# V1.net
KiCad netlist of a schematic drawn in EAGLE
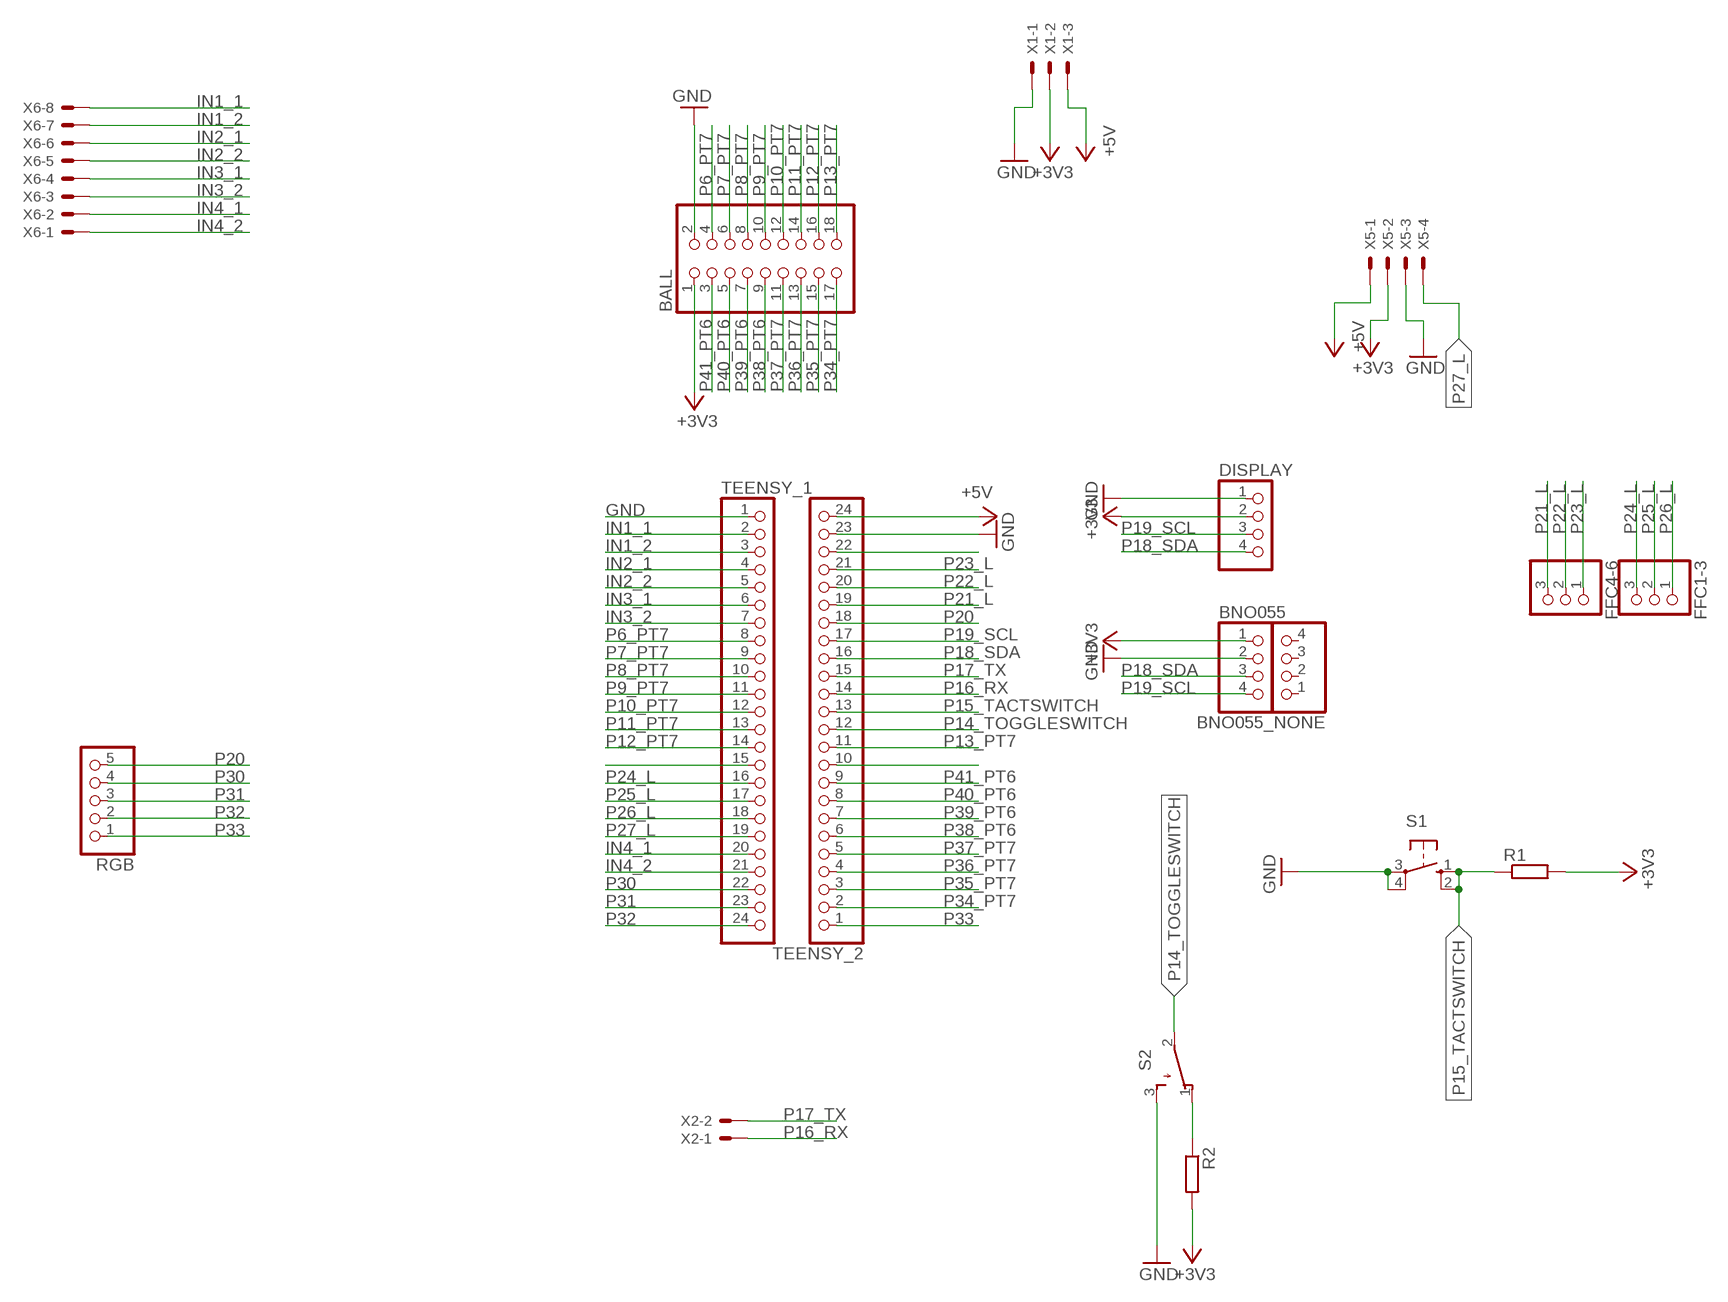
[diagram p0: schematic, sheet 1]

(export (version "E")
  (design (tool "Eeschema 10.0.6"))
  (components
    (comp (ref "BALL")
      (value "PINHD-2X9")
      (footprint "eagle-import:2X09")
      (libsource (lib "eagle-import") (part "PINHD-2X9"))
    )
    (comp (ref "BNO055")
      (value "PINHD-1X4")
      (footprint "eagle-import:1X04")
      (libsource (lib "eagle-import") (part "PINHD-1X4"))
    )
    (comp (ref "BNO055_NONE")
      (value "PINHD-1X4")
      (footprint "eagle-import:1X04")
      (libsource (lib "eagle-import") (part "PINHD-1X4"))
    )
    (comp (ref "DISPLAY")
      (value "PINHD-1X04_2.54-S")
      (footprint "eagle-import:1X04-S")
      (libsource (lib "eagle-import") (part "PINHD-1X04_2.54-S"))
    )
    (comp (ref "FFC1-3")
      (value "PINHD-1X03_2.54-S")
      (footprint "eagle-import:1X03-S")
      (libsource (lib "eagle-import") (part "PINHD-1X03_2.54-S"))
    )
    (comp (ref "FFC4-6")
      (value "PINHD-1X03_2.54-S")
      (footprint "eagle-import:1X03-S")
      (libsource (lib "eagle-import") (part "PINHD-1X03_2.54-S"))
    )
    (comp (ref "R1")
      (value "R-EU_0207/10")
      (footprint "eagle-import:0207_10")
      (libsource (lib "eagle-import") (part "R-EU_0207/10"))
    )
    (comp (ref "R2")
      (value "R-EU_0207/10")
      (footprint "eagle-import:0207_10")
      (libsource (lib "eagle-import") (part "R-EU_0207/10"))
    )
    (comp (ref "RGB")
      (value "PINHD-1X05_2.54-S")
      (footprint "eagle-import:1X05-S")
      (libsource (lib "eagle-import") (part "PINHD-1X05_2.54-S"))
    )
    (comp (ref "S1")
      (value "40-XX")
      (footprint "eagle-import:B3F-40XX")
      (fields (field (name "MF") "OMRON COMPONENTS USA") (field (name "MPN") "B3F-4000"))
      (libsource (lib "eagle-import") (part "40-XX"))
    )
    (comp (ref "S2")
      (value "TL32PO")
      (footprint "eagle-import:TL3XPO")
      (libsource (lib "eagle-import") (part "TL32PO"))
    )
    (comp (ref "TEENSY_1")
      (value "PINHD-1X24")
      (footprint "eagle-import:1X24")
      (libsource (lib "eagle-import") (part "PINHD-1X24"))
    )
    (comp (ref "TEENSY_2")
      (value "PINHD-1X24")
      (footprint "eagle-import:1X24")
      (libsource (lib "eagle-import") (part "PINHD-1X24"))
    )
    (comp (ref "X1")
      (value "JST-XH-03-PIN-ROUND-PAD")
      (footprint "eagle-import:JST-XH-03-PACKAGE-ROUND-PAD")
      (libsource (lib "eagle-import") (part "JST-XH-03-PIN-ROUND-PAD"))
    )
    (comp (ref "X2")
      (value "JST-XH-02-PIN-ROUND-PAD")
      (footprint "eagle-import:JST-XH-02-PACKAGE-ROUND-PAD")
      (libsource (lib "eagle-import") (part "JST-XH-02-PIN-ROUND-PAD"))
    )
    (comp (ref "X5")
      (value "JST-XH-04-PIN-ROUND-PAD")
      (footprint "eagle-import:JST-XH-04-PACKAGE-ROUND-PAD")
      (libsource (lib "eagle-import") (part "JST-XH-04-PIN-ROUND-PAD"))
    )
    (comp (ref "X6")
      (value "JST-XH-08-PIN-ROUND-PAD")
      (footprint "eagle-import:JST-XH-08-PACKAGE-ROUND-PAD")
      (libsource (lib "eagle-import") (part "JST-XH-08-PIN-ROUND-PAD"))
    )
  )
  (nets
    (net (code "1") (name "+3V3") (class "Default")
      (node (ref "BALL") (pin "1") (pinfunction "1_1") (pintype "passive"))
      (node (ref "BNO055") (pin "1") (pinfunction "1_1") (pintype "passive"))
      (node (ref "DISPLAY") (pin "2") (pinfunction "2_2") (pintype "passive"))
      (node (ref "R1") (pin "2") (pinfunction "2_2") (pintype "passive"))
      (node (ref "R2") (pin "2") (pinfunction "2_2") (pintype "passive"))
      (node (ref "X1") (pin "2") (pinfunction "S_2") (pintype "passive"))
      (node (ref "X5") (pin "2") (pinfunction "S_2") (pintype "passive"))
    )
    (net (code "2") (name "+5V") (class "Default")
      (node (ref "TEENSY_2") (pin "24") (pinfunction "24_24") (pintype "passive"))
      (node (ref "X1") (pin "3") (pinfunction "S_3") (pintype "passive"))
      (node (ref "X5") (pin "1") (pinfunction "S_1") (pintype "passive"))
    )
    (net (code "3") (name "/IN1_1") (class "Default")
      (node (ref "TEENSY_1") (pin "2") (pinfunction "2_2") (pintype "passive"))
      (node (ref "X6") (pin "8") (pinfunction "S_8") (pintype "passive"))
    )
    (net (code "4") (name "/IN1_2") (class "Default")
      (node (ref "TEENSY_1") (pin "3") (pinfunction "3_3") (pintype "passive"))
      (node (ref "X6") (pin "7") (pinfunction "S_7") (pintype "passive"))
    )
    (net (code "5") (name "/IN2_1") (class "Default")
      (node (ref "TEENSY_1") (pin "4") (pinfunction "4_4") (pintype "passive"))
      (node (ref "X6") (pin "6") (pinfunction "S_6") (pintype "passive"))
    )
    (net (code "6") (name "/IN2_2") (class "Default")
      (node (ref "TEENSY_1") (pin "5") (pinfunction "5_5") (pintype "passive"))
      (node (ref "X6") (pin "5") (pinfunction "S_5") (pintype "passive"))
    )
    (net (code "7") (name "/IN3_1") (class "Default")
      (node (ref "TEENSY_1") (pin "6") (pinfunction "6_6") (pintype "passive"))
      (node (ref "X6") (pin "4") (pinfunction "S_4") (pintype "passive"))
    )
    (net (code "8") (name "/IN3_2") (class "Default")
      (node (ref "TEENSY_1") (pin "7") (pinfunction "7_7") (pintype "passive"))
      (node (ref "X6") (pin "3") (pinfunction "S_3") (pintype "passive"))
    )
    (net (code "9") (name "/IN4_1") (class "Default")
      (node (ref "TEENSY_1") (pin "20") (pinfunction "20_20") (pintype "passive"))
      (node (ref "X6") (pin "2") (pinfunction "S_2") (pintype "passive"))
    )
    (net (code "10") (name "/IN4_2") (class "Default")
      (node (ref "TEENSY_1") (pin "21") (pinfunction "21_21") (pintype "passive"))
      (node (ref "X6") (pin "1") (pinfunction "S_1") (pintype "passive"))
    )
    (net (code "11") (name "/P6_PT7") (class "Default")
      (node (ref "BALL") (pin "4") (pinfunction "4_4") (pintype "passive"))
      (node (ref "TEENSY_1") (pin "8") (pinfunction "8_8") (pintype "passive"))
    )
    (net (code "12") (name "/P7_PT7") (class "Default")
      (node (ref "BALL") (pin "6") (pinfunction "6_6") (pintype "passive"))
      (node (ref "TEENSY_1") (pin "9") (pinfunction "9_9") (pintype "passive"))
    )
    (net (code "13") (name "/P8_PT7") (class "Default")
      (node (ref "BALL") (pin "8") (pinfunction "8_8") (pintype "passive"))
      (node (ref "TEENSY_1") (pin "10") (pinfunction "10_10") (pintype "passive"))
    )
    (net (code "14") (name "/P9_PT7") (class "Default")
      (node (ref "BALL") (pin "10") (pinfunction "10_10") (pintype "passive"))
      (node (ref "TEENSY_1") (pin "11") (pinfunction "11_11") (pintype "passive"))
    )
    (net (code "15") (name "/P10_PT7") (class "Default")
      (node (ref "BALL") (pin "12") (pinfunction "12_12") (pintype "passive"))
      (node (ref "TEENSY_1") (pin "12") (pinfunction "12_12") (pintype "passive"))
    )
    (net (code "16") (name "/P11_PT7") (class "Default")
      (node (ref "BALL") (pin "14") (pinfunction "14_14") (pintype "passive"))
      (node (ref "TEENSY_1") (pin "13") (pinfunction "13_13") (pintype "passive"))
    )
    (net (code "17") (name "/P12_PT7") (class "Default")
      (node (ref "BALL") (pin "16") (pinfunction "16_16") (pintype "passive"))
      (node (ref "TEENSY_1") (pin "14") (pinfunction "14_14") (pintype "passive"))
    )
    (net (code "18") (name "/P13_PT7") (class "Default")
      (node (ref "BALL") (pin "18") (pinfunction "18_18") (pintype "passive"))
      (node (ref "TEENSY_2") (pin "11") (pinfunction "11_11") (pintype "passive"))
    )
    (net (code "19") (name "/P16_RX") (class "Default")
      (node (ref "TEENSY_2") (pin "14") (pinfunction "14_14") (pintype "passive"))
      (node (ref "X2") (pin "1") (pinfunction "S_1") (pintype "passive"))
    )
    (net (code "20") (name "/P17_TX") (class "Default")
      (node (ref "TEENSY_2") (pin "15") (pinfunction "15_15") (pintype "passive"))
      (node (ref "X2") (pin "2") (pinfunction "S_2") (pintype "passive"))
    )
    (net (code "21") (name "/P18_SDA") (class "Default")
      (node (ref "BNO055") (pin "3") (pinfunction "3_3") (pintype "passive"))
      (node (ref "DISPLAY") (pin "4") (pinfunction "4_4") (pintype "passive"))
      (node (ref "TEENSY_2") (pin "16") (pinfunction "16_16") (pintype "passive"))
    )
    (net (code "22") (name "/P19_SCL") (class "Default")
      (node (ref "BNO055") (pin "4") (pinfunction "4_4") (pintype "passive"))
      (node (ref "DISPLAY") (pin "3") (pinfunction "3_3") (pintype "passive"))
      (node (ref "TEENSY_2") (pin "17") (pinfunction "17_17") (pintype "passive"))
    )
    (net (code "23") (name "/P20") (class "Default")
      (node (ref "RGB") (pin "5") (pinfunction "5_5") (pintype "passive"))
      (node (ref "TEENSY_2") (pin "18") (pinfunction "18_18") (pintype "passive"))
    )
    (net (code "24") (name "/P21_L") (class "Default")
      (node (ref "FFC4-6") (pin "3") (pinfunction "3_3") (pintype "passive"))
      (node (ref "TEENSY_2") (pin "19") (pinfunction "19_19") (pintype "passive"))
    )
    (net (code "25") (name "/P22_L") (class "Default")
      (node (ref "FFC4-6") (pin "2") (pinfunction "2_2") (pintype "passive"))
      (node (ref "TEENSY_2") (pin "20") (pinfunction "20_20") (pintype "passive"))
    )
    (net (code "26") (name "/P23_L") (class "Default")
      (node (ref "FFC4-6") (pin "1") (pinfunction "1_1") (pintype "passive"))
      (node (ref "TEENSY_2") (pin "21") (pinfunction "21_21") (pintype "passive"))
    )
    (net (code "27") (name "/P24_L") (class "Default")
      (node (ref "FFC1-3") (pin "3") (pinfunction "3_3") (pintype "passive"))
      (node (ref "TEENSY_1") (pin "16") (pinfunction "16_16") (pintype "passive"))
    )
    (net (code "28") (name "/P25_L") (class "Default")
      (node (ref "FFC1-3") (pin "2") (pinfunction "2_2") (pintype "passive"))
      (node (ref "TEENSY_1") (pin "17") (pinfunction "17_17") (pintype "passive"))
    )
    (net (code "29") (name "/P26_L") (class "Default")
      (node (ref "FFC1-3") (pin "1") (pinfunction "1_1") (pintype "passive"))
      (node (ref "TEENSY_1") (pin "18") (pinfunction "18_18") (pintype "passive"))
    )
    (net (code "30") (name "/P30") (class "Default")
      (node (ref "RGB") (pin "4") (pinfunction "4_4") (pintype "passive"))
      (node (ref "TEENSY_1") (pin "22") (pinfunction "22_22") (pintype "passive"))
    )
    (net (code "31") (name "/P31") (class "Default")
      (node (ref "RGB") (pin "3") (pinfunction "3_3") (pintype "passive"))
      (node (ref "TEENSY_1") (pin "23") (pinfunction "23_23") (pintype "passive"))
    )
    (net (code "32") (name "/P32") (class "Default")
      (node (ref "RGB") (pin "2") (pinfunction "2_2") (pintype "passive"))
      (node (ref "TEENSY_1") (pin "24") (pinfunction "24_24") (pintype "passive"))
    )
    (net (code "33") (name "/P33") (class "Default")
      (node (ref "RGB") (pin "1") (pinfunction "1_1") (pintype "passive"))
      (node (ref "TEENSY_2") (pin "1") (pinfunction "1_1") (pintype "passive"))
    )
    (net (code "34") (name "/P34_PT7") (class "Default")
      (node (ref "BALL") (pin "17") (pinfunction "17_17") (pintype "passive"))
      (node (ref "TEENSY_2") (pin "2") (pinfunction "2_2") (pintype "passive"))
    )
    (net (code "35") (name "/P35_PT7") (class "Default")
      (node (ref "BALL") (pin "15") (pinfunction "15_15") (pintype "passive"))
      (node (ref "TEENSY_2") (pin "3") (pinfunction "3_3") (pintype "passive"))
    )
    (net (code "36") (name "/P36_PT7") (class "Default")
      (node (ref "BALL") (pin "13") (pinfunction "13_13") (pintype "passive"))
      (node (ref "TEENSY_2") (pin "4") (pinfunction "4_4") (pintype "passive"))
    )
    (net (code "37") (name "/P37_PT7") (class "Default")
      (node (ref "BALL") (pin "11") (pinfunction "11_11") (pintype "passive"))
      (node (ref "TEENSY_2") (pin "5") (pinfunction "5_5") (pintype "passive"))
    )
    (net (code "38") (name "/P38_PT6") (class "Default")
      (node (ref "BALL") (pin "9") (pinfunction "9_9") (pintype "passive"))
      (node (ref "TEENSY_2") (pin "6") (pinfunction "6_6") (pintype "passive"))
    )
    (net (code "39") (name "/P39_PT6") (class "Default")
      (node (ref "BALL") (pin "7") (pinfunction "7_7") (pintype "passive"))
      (node (ref "TEENSY_2") (pin "7") (pinfunction "7_7") (pintype "passive"))
    )
    (net (code "40") (name "/P40_PT6") (class "Default")
      (node (ref "BALL") (pin "5") (pinfunction "5_5") (pintype "passive"))
      (node (ref "TEENSY_2") (pin "8") (pinfunction "8_8") (pintype "passive"))
    )
    (net (code "41") (name "/P41_PT6") (class "Default")
      (node (ref "BALL") (pin "3") (pinfunction "3_3") (pintype "passive"))
      (node (ref "TEENSY_2") (pin "9") (pinfunction "9_9") (pintype "passive"))
    )
    (net (code "42") (name "GND") (class "Default")
      (node (ref "BALL") (pin "2") (pinfunction "2_2") (pintype "passive"))
      (node (ref "BNO055") (pin "2") (pinfunction "2_2") (pintype "passive"))
      (node (ref "DISPLAY") (pin "1") (pinfunction "1_1") (pintype "passive"))
      (node (ref "S1") (pin "3") (pinfunction "P_3") (pintype "passive"))
      (node (ref "S1") (pin "4") (pinfunction "P1_4") (pintype "passive"))
      (node (ref "S2") (pin "3") (pinfunction "S_3") (pintype "passive"))
      (node (ref "TEENSY_1") (pin "1") (pinfunction "1_1") (pintype "passive"))
      (node (ref "TEENSY_2") (pin "23") (pinfunction "23_23") (pintype "passive"))
      (node (ref "X1") (pin "1") (pinfunction "S_1") (pintype "passive"))
      (node (ref "X5") (pin "3") (pinfunction "S_3") (pintype "passive"))
    )
    (net (code "43") (name "Net-(S2-O)") (class "Default")
      (node (ref "R2") (pin "1") (pinfunction "1_1") (pintype "passive"))
      (node (ref "S2") (pin "1") (pinfunction "O_1") (pintype "passive"))
    )
    (net (code "44") (name "P14_TOGGLESWITCH") (class "Default")
      (node (ref "S2") (pin "2") (pinfunction "P_2") (pintype "passive"))
      (node (ref "TEENSY_2") (pin "12") (pinfunction "12_12") (pintype "passive"))
    )
    (net (code "45") (name "P15_TACTSWITCH") (class "Default")
      (node (ref "R1") (pin "1") (pinfunction "1_1") (pintype "passive"))
      (node (ref "S1") (pin "1") (pinfunction "S_1") (pintype "passive"))
      (node (ref "S1") (pin "2") (pinfunction "S1_2") (pintype "passive"))
      (node (ref "TEENSY_2") (pin "13") (pinfunction "13_13") (pintype "passive"))
    )
    (net (code "46") (name "P27_L") (class "Default")
      (node (ref "TEENSY_1") (pin "19") (pinfunction "19_19") (pintype "passive"))
      (node (ref "X5") (pin "4") (pinfunction "S_4") (pintype "passive"))
    )
    (net (code "47") (name "unconnected-(BNO055_NONE-Pad1)") (class "Default")
      (node (ref "BNO055_NONE") (pin "1") (pinfunction "1_1") (pintype "passive"))
    )
    (net (code "48") (name "unconnected-(BNO055_NONE-Pad2)") (class "Default")
      (node (ref "BNO055_NONE") (pin "2") (pinfunction "2_2") (pintype "passive"))
    )
    (net (code "49") (name "unconnected-(BNO055_NONE-Pad3)") (class "Default")
      (node (ref "BNO055_NONE") (pin "3") (pinfunction "3_3") (pintype "passive"))
    )
    (net (code "50") (name "unconnected-(BNO055_NONE-Pad4)") (class "Default")
      (node (ref "BNO055_NONE") (pin "4") (pinfunction "4_4") (pintype "passive"))
    )
    (net (code "51") (name "unconnected-(TEENSY_1-Pad15)") (class "Default")
      (node (ref "TEENSY_1") (pin "15") (pinfunction "15_15") (pintype "passive"))
    )
    (net (code "52") (name "unconnected-(TEENSY_2-Pad10)") (class "Default")
      (node (ref "TEENSY_2") (pin "10") (pinfunction "10_10") (pintype "passive"))
    )
    (net (code "53") (name "unconnected-(TEENSY_2-Pad22)") (class "Default")
      (node (ref "TEENSY_2") (pin "22") (pinfunction "22_22") (pintype "passive"))
    )
  )
)
